# ATtiny_LED_badge.net
KiCad netlist of a schematic drawn in EAGLE
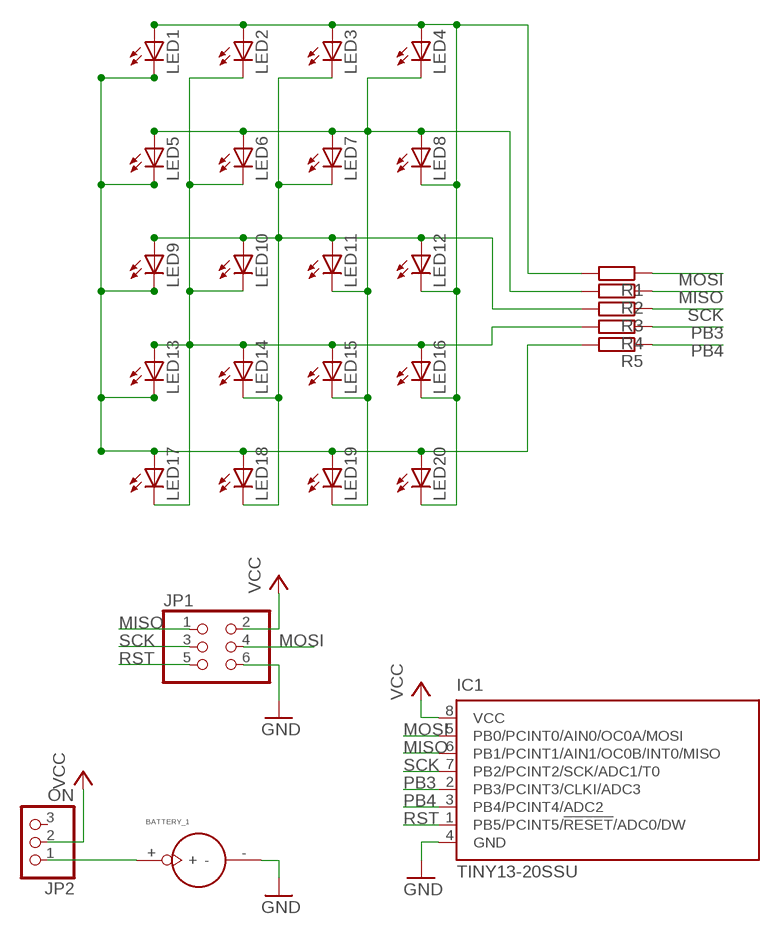
[diagram p0: schematic, sheet 1]

(export (version "E")
  (design (tool "Eeschema 10.0.6"))
  (components
    (comp (ref "BATTERY_1")
      (value "BATTERY_1236_C")
      (footprint "eagle-import:BATTERY_1236_C")
      (libsource (lib "eagle-import") (part "BATTERY_1236_C"))
    )
    (comp (ref "IC1")
      (value "TINY13-20SSU")
      (footprint "eagle-import:8S1")
      (fields (field (name "MPN") "ATTINY13-20SSU"))
      (libsource (lib "eagle-import") (part "TINY13SSU-20"))
    )
    (comp (ref "JP1")
      (value "PINHD-2X3")
      (footprint "eagle-import:2X03")
      (libsource (lib "eagle-import") (part "PINHD-2X3"))
    )
    (comp (ref "JP2")
      (value "ON")
      (footprint "eagle-import:1X03")
      (libsource (lib "eagle-import") (part "PINHD-1X3"))
    )
    (comp (ref "LED1")
      (value "LED3MM")
      (footprint "eagle-import:LED3MM")
      (libsource (lib "eagle-import") (part "LED3MM"))
    )
    (comp (ref "LED2")
      (value "LED3MM")
      (footprint "eagle-import:LED3MM")
      (libsource (lib "eagle-import") (part "LED3MM"))
    )
    (comp (ref "LED3")
      (value "LED3MM")
      (footprint "eagle-import:LED3MM")
      (libsource (lib "eagle-import") (part "LED3MM"))
    )
    (comp (ref "LED4")
      (value "LED3MM")
      (footprint "eagle-import:LED3MM")
      (libsource (lib "eagle-import") (part "LED3MM"))
    )
    (comp (ref "LED5")
      (value "LED3MM")
      (footprint "eagle-import:LED3MM")
      (libsource (lib "eagle-import") (part "LED3MM"))
    )
    (comp (ref "LED6")
      (value "LED3MM")
      (footprint "eagle-import:LED3MM")
      (libsource (lib "eagle-import") (part "LED3MM"))
    )
    (comp (ref "LED7")
      (value "LED3MM")
      (footprint "eagle-import:LED3MM")
      (libsource (lib "eagle-import") (part "LED3MM"))
    )
    (comp (ref "LED8")
      (value "LED3MM")
      (footprint "eagle-import:LED3MM")
      (libsource (lib "eagle-import") (part "LED3MM"))
    )
    (comp (ref "LED9")
      (value "LED3MM")
      (footprint "eagle-import:LED3MM")
      (libsource (lib "eagle-import") (part "LED3MM"))
    )
    (comp (ref "LED10")
      (value "LED3MM")
      (footprint "eagle-import:LED3MM")
      (libsource (lib "eagle-import") (part "LED3MM"))
    )
    (comp (ref "LED11")
      (value "LED3MM")
      (footprint "eagle-import:LED3MM")
      (libsource (lib "eagle-import") (part "LED3MM"))
    )
    (comp (ref "LED12")
      (value "LED3MM")
      (footprint "eagle-import:LED3MM")
      (libsource (lib "eagle-import") (part "LED3MM"))
    )
    (comp (ref "LED13")
      (value "LED3MM")
      (footprint "eagle-import:LED3MM")
      (libsource (lib "eagle-import") (part "LED3MM"))
    )
    (comp (ref "LED14")
      (value "LED3MM")
      (footprint "eagle-import:LED3MM")
      (libsource (lib "eagle-import") (part "LED3MM"))
    )
    (comp (ref "LED15")
      (value "LED3MM")
      (footprint "eagle-import:LED3MM")
      (libsource (lib "eagle-import") (part "LED3MM"))
    )
    (comp (ref "LED16")
      (value "LED3MM")
      (footprint "eagle-import:LED3MM")
      (libsource (lib "eagle-import") (part "LED3MM"))
    )
    (comp (ref "LED17")
      (value "LED3MM")
      (footprint "eagle-import:LED3MM")
      (libsource (lib "eagle-import") (part "LED3MM"))
    )
    (comp (ref "LED18")
      (value "LED3MM")
      (footprint "eagle-import:LED3MM")
      (libsource (lib "eagle-import") (part "LED3MM"))
    )
    (comp (ref "LED19")
      (value "LED3MM")
      (footprint "eagle-import:LED3MM")
      (libsource (lib "eagle-import") (part "LED3MM"))
    )
    (comp (ref "LED20")
      (value "LED3MM")
      (footprint "eagle-import:LED3MM")
      (libsource (lib "eagle-import") (part "LED3MM"))
    )
    (comp (ref "R1")
      (value "R-EU_0207/7")
      (footprint "eagle-import:0207_7")
      (libsource (lib "eagle-import") (part "R-EU_0207/7"))
    )
    (comp (ref "R2")
      (value "R-EU_0207/7")
      (footprint "eagle-import:0207_7")
      (libsource (lib "eagle-import") (part "R-EU_0207/7"))
    )
    (comp (ref "R3")
      (value "R-EU_0207/7")
      (footprint "eagle-import:0207_7")
      (libsource (lib "eagle-import") (part "R-EU_0207/7"))
    )
    (comp (ref "R4")
      (value "R-EU_0207/7")
      (footprint "eagle-import:0207_7")
      (libsource (lib "eagle-import") (part "R-EU_0207/7"))
    )
    (comp (ref "R5")
      (value "R-EU_0207/7")
      (footprint "eagle-import:0207_7")
      (libsource (lib "eagle-import") (part "R-EU_0207/7"))
    )
  )
  (nets
    (net (code "1") (name "/MISO") (class "Default")
      (node (ref "IC1") (pin "6") (pinfunction "PB1/PCINT1/AIN1/OC0B/INT0/MISO_6") (pintype "bidirectional"))
      (node (ref "JP1") (pin "1") (pinfunction "1_1") (pintype "passive"))
      (node (ref "R2") (pin "1") (pinfunction "1_1") (pintype "passive"))
    )
    (net (code "2") (name "/MOSI") (class "Default")
      (node (ref "IC1") (pin "5") (pinfunction "PB0/PCINT0/AIN0/OC0A/MOSI_5") (pintype "bidirectional"))
      (node (ref "JP1") (pin "4") (pinfunction "4_4") (pintype "passive"))
      (node (ref "R1") (pin "1") (pinfunction "1_1") (pintype "passive"))
    )
    (net (code "3") (name "/PB3") (class "Default")
      (node (ref "IC1") (pin "2") (pinfunction "PB3/PCINT3/CLKI/ADC3_2") (pintype "bidirectional"))
      (node (ref "R4") (pin "1") (pinfunction "1_1") (pintype "passive"))
    )
    (net (code "4") (name "/PB4") (class "Default")
      (node (ref "IC1") (pin "3") (pinfunction "PB4/PCINT4/ADC2_3") (pintype "bidirectional"))
      (node (ref "R5") (pin "1") (pinfunction "1_1") (pintype "passive"))
    )
    (net (code "5") (name "/RST") (class "Default")
      (node (ref "IC1") (pin "1") (pinfunction "PB5/PCINT5/~{RESET}/ADC0/DW_1") (pintype "bidirectional"))
      (node (ref "JP1") (pin "5") (pinfunction "5_5") (pintype "passive"))
    )
    (net (code "6") (name "/SCK") (class "Default")
      (node (ref "IC1") (pin "7") (pinfunction "PB2/PCINT2/SCK/ADC1/T0_7") (pintype "bidirectional"))
      (node (ref "JP1") (pin "3") (pinfunction "3_3") (pintype "passive"))
      (node (ref "R3") (pin "1") (pinfunction "1_1") (pintype "passive"))
    )
    (net (code "7") (name "GND") (class "Default")
      (node (ref "BATTERY_1") (pin "-") (pinfunction "-_-") (pintype "bidirectional"))
      (node (ref "IC1") (pin "4") (pinfunction "GND_4") (pintype "power_in"))
      (node (ref "JP1") (pin "6") (pinfunction "6_6") (pintype "passive"))
    )
    (net (code "8") (name "Net-(BATTERY_1-Pad+)") (class "Default")
      (node (ref "BATTERY_1") (pin "+") (pinfunction "+_+") (pintype "bidirectional"))
      (node (ref "JP2") (pin "1") (pinfunction "1_1") (pintype "passive"))
    )
    (net (code "9") (name "Net-(LED1-C)") (class "Default")
      (node (ref "LED1") (pin "K") (pinfunction "C_K") (pintype "passive"))
      (node (ref "LED13") (pin "K") (pinfunction "C_K") (pintype "passive"))
      (node (ref "LED17") (pin "A") (pinfunction "A_A") (pintype "passive"))
      (node (ref "LED18") (pin "A") (pinfunction "A_A") (pintype "passive"))
      (node (ref "LED19") (pin "A") (pinfunction "A_A") (pintype "passive"))
      (node (ref "LED20") (pin "A") (pinfunction "A_A") (pintype "passive"))
      (node (ref "LED5") (pin "K") (pinfunction "C_K") (pintype "passive"))
      (node (ref "LED9") (pin "K") (pinfunction "C_K") (pintype "passive"))
      (node (ref "R5") (pin "2") (pinfunction "2_2") (pintype "passive"))
    )
    (net (code "10") (name "Net-(LED10-C)") (class "Default")
      (node (ref "LED10") (pin "K") (pinfunction "C_K") (pintype "passive"))
      (node (ref "LED13") (pin "A") (pinfunction "A_A") (pintype "passive"))
      (node (ref "LED14") (pin "A") (pinfunction "A_A") (pintype "passive"))
      (node (ref "LED15") (pin "A") (pinfunction "A_A") (pintype "passive"))
      (node (ref "LED16") (pin "A") (pinfunction "A_A") (pintype "passive"))
      (node (ref "LED17") (pin "K") (pinfunction "C_K") (pintype "passive"))
      (node (ref "LED2") (pin "K") (pinfunction "C_K") (pintype "passive"))
      (node (ref "LED6") (pin "K") (pinfunction "C_K") (pintype "passive"))
      (node (ref "R4") (pin "2") (pinfunction "2_2") (pintype "passive"))
    )
    (net (code "11") (name "Net-(LED11-C)") (class "Default")
      (node (ref "LED11") (pin "K") (pinfunction "C_K") (pintype "passive"))
      (node (ref "LED15") (pin "K") (pinfunction "C_K") (pintype "passive"))
      (node (ref "LED19") (pin "K") (pinfunction "C_K") (pintype "passive"))
      (node (ref "LED4") (pin "K") (pinfunction "C_K") (pintype "passive"))
      (node (ref "LED5") (pin "A") (pinfunction "A_A") (pintype "passive"))
      (node (ref "LED6") (pin "A") (pinfunction "A_A") (pintype "passive"))
      (node (ref "LED7") (pin "A") (pinfunction "A_A") (pintype "passive"))
      (node (ref "LED8") (pin "A") (pinfunction "A_A") (pintype "passive"))
      (node (ref "R2") (pin "2") (pinfunction "2_2") (pintype "passive"))
    )
    (net (code "12") (name "Net-(LED12-C)") (class "Default")
      (node (ref "LED1") (pin "A") (pinfunction "A_A") (pintype "passive"))
      (node (ref "LED12") (pin "K") (pinfunction "C_K") (pintype "passive"))
      (node (ref "LED16") (pin "K") (pinfunction "C_K") (pintype "passive"))
      (node (ref "LED2") (pin "A") (pinfunction "A_A") (pintype "passive"))
      (node (ref "LED20") (pin "K") (pinfunction "C_K") (pintype "passive"))
      (node (ref "LED3") (pin "A") (pinfunction "A_A") (pintype "passive"))
      (node (ref "LED4") (pin "A") (pinfunction "A_A") (pintype "passive"))
      (node (ref "LED8") (pin "K") (pinfunction "C_K") (pintype "passive"))
      (node (ref "R1") (pin "2") (pinfunction "2_2") (pintype "passive"))
    )
    (net (code "13") (name "Net-(LED14-C)") (class "Default")
      (node (ref "LED10") (pin "A") (pinfunction "A_A") (pintype "passive"))
      (node (ref "LED11") (pin "A") (pinfunction "A_A") (pintype "passive"))
      (node (ref "LED12") (pin "A") (pinfunction "A_A") (pintype "passive"))
      (node (ref "LED14") (pin "K") (pinfunction "C_K") (pintype "passive"))
      (node (ref "LED18") (pin "K") (pinfunction "C_K") (pintype "passive"))
      (node (ref "LED3") (pin "K") (pinfunction "C_K") (pintype "passive"))
      (node (ref "LED7") (pin "K") (pinfunction "C_K") (pintype "passive"))
      (node (ref "LED9") (pin "A") (pinfunction "A_A") (pintype "passive"))
      (node (ref "R3") (pin "2") (pinfunction "2_2") (pintype "passive"))
    )
    (net (code "14") (name "VCC") (class "Default")
      (node (ref "IC1") (pin "8") (pinfunction "VCC_8") (pintype "power_in"))
      (node (ref "JP1") (pin "2") (pinfunction "2_2") (pintype "passive"))
      (node (ref "JP2") (pin "2") (pinfunction "2_2") (pintype "passive"))
    )
    (net (code "15") (name "unconnected-(JP2-Pad3)") (class "Default")
      (node (ref "JP2") (pin "3") (pinfunction "3_3") (pintype "passive"))
    )
  )
)
